# main.net
KiCad netlist of a schematic drawn in Altium Designer
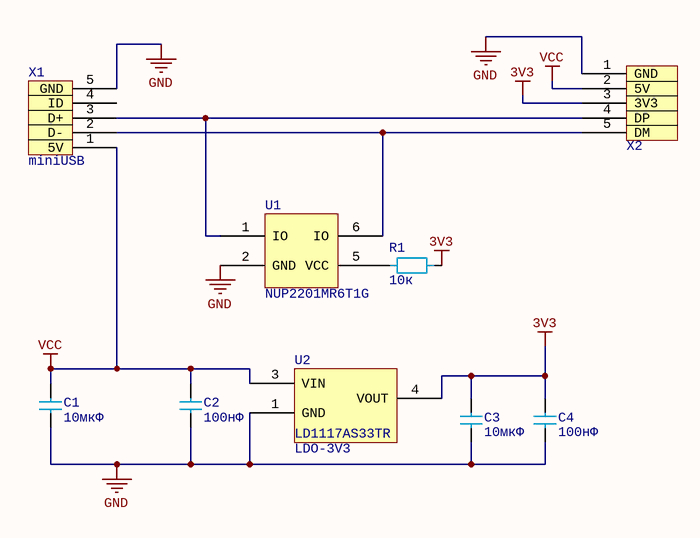
[diagram p0: main.SchDoc]

(export (version "E")
  (design (tool "Eeschema 10.0.6"))
  (components
    (comp (ref "C1")
      (value "C-керамика")
      (footprint "CAPC2012-0805")
      (description "Керамический конденсатор")
      (fields (field (name "CAPACITY") "10мкФ"))
      (libsource (lib "Passive") (part "C-керамика"))
    )
    (comp (ref "C2")
      (value "C-керамика")
      (footprint "CAPC2012-0805")
      (description "Керамический конденсатор")
      (fields (field (name "CAPACITY") "100нФ"))
      (libsource (lib "Passive") (part "C-керамика"))
    )
    (comp (ref "C3")
      (value "C-керамика")
      (footprint "CAPC2012-0805")
      (description "Керамический конденсатор")
      (fields (field (name "CAPACITY") "10мкФ"))
      (libsource (lib "Passive") (part "C-керамика"))
    )
    (comp (ref "C4")
      (value "C-керамика")
      (footprint "CAPC2012-0805")
      (description "Керамический конденсатор")
      (fields (field (name "CAPACITY") "100нФ"))
      (libsource (lib "Passive") (part "C-керамика"))
    )
    (comp (ref "R1")
      (value "R")
      (footprint "CR2012-0805")
      (description "Резистор")
      (fields (field (name "RESISTANCE") "10к"))
      (libsource (lib "Passive") (part "R"))
    )
    (comp (ref "U1")
      (value "NUP2201MR6T1G")
      (footprint "SOT-23-6")
      (libsource (lib "main") (part "NUP2201MR6T1G"))
    )
    (comp (ref "U2")
      (value "LDO-3V3")
      (footprint "SOT-223")
      (description "Voltage regulator, 3v3")
      (libsource (lib "Active") (part "LD1117AS33TR"))
    )
    (comp (ref "X1") (value "miniUSB") (footprint "USB/SM0.8-6H5") (libsource (lib "main") (part "miniUSB")))
    (comp (ref "X2") (value "*") (footprint "PBS_5-1") (libsource (lib "main") (part "PBS-5-1")))
  )
  (nets
    (net (code "1") (name "3V3") (class "Default")
      (node (ref "C3") (pin "1") (pinfunction "1_1") (pintype "passive"))
      (node (ref "C4") (pin "1") (pinfunction "1_1") (pintype "passive"))
      (node (ref "R1") (pin "2") (pinfunction "2_2") (pintype "passive"))
      (node (ref "U2") (pin "4") (pinfunction "VOUT_4") (pintype "passive"))
      (node (ref "X2") (pin "3") (pinfunction "3V3_3") (pintype "passive"))
    )
    (net (code "2") (name "GND") (class "Default")
      (node (ref "C1") (pin "2") (pinfunction "2_2") (pintype "passive"))
      (node (ref "C2") (pin "2") (pinfunction "2_2") (pintype "passive"))
      (node (ref "C3") (pin "2") (pinfunction "2_2") (pintype "passive"))
      (node (ref "C4") (pin "2") (pinfunction "2_2") (pintype "passive"))
      (node (ref "U1") (pin "2") (pinfunction "GND_2") (pintype "passive"))
      (node (ref "U2") (pin "1") (pinfunction "GND_1") (pintype "passive"))
      (node (ref "X1") (pin "5") (pinfunction "GND_5") (pintype "passive"))
      (node (ref "X2") (pin "1") (pinfunction "GND_1") (pintype "passive"))
    )
    (net (code "3") (name "Net-(U1-VCC)") (class "Default")
      (node (ref "R1") (pin "1") (pinfunction "1_1") (pintype "passive"))
      (node (ref "U1") (pin "5") (pinfunction "VCC_5") (pintype "passive"))
    )
    (net (code "4") (name "Net-(X1-D+)") (class "Default")
      (node (ref "U1") (pin "1") (pinfunction "IO_1") (pintype "passive"))
      (node (ref "X1") (pin "3") (pinfunction "D+_3") (pintype "passive"))
      (node (ref "X2") (pin "4") (pinfunction "DP_4") (pintype "passive"))
    )
    (net (code "5") (name "Net-(X1-D-)") (class "Default")
      (node (ref "U1") (pin "6") (pinfunction "IO_6") (pintype "passive"))
      (node (ref "X1") (pin "2") (pinfunction "D-_2") (pintype "passive"))
      (node (ref "X2") (pin "5") (pinfunction "DM_5") (pintype "passive"))
    )
    (net (code "6") (name "VCC") (class "Default")
      (node (ref "C1") (pin "1") (pinfunction "1_1") (pintype "passive"))
      (node (ref "C2") (pin "1") (pinfunction "1_1") (pintype "passive"))
      (node (ref "U2") (pin "3") (pinfunction "VIN_3") (pintype "passive"))
      (node (ref "X1") (pin "1") (pinfunction "5V_1") (pintype "passive"))
      (node (ref "X2") (pin "2") (pinfunction "5V_2") (pintype "passive"))
    )
    (net (code "7") (name "unconnected-(X1-ID-Pad4)") (class "Default")
      (node (ref "X1") (pin "4") (pinfunction "ID_4") (pintype "passive"))
    )
  )
)
